# MCU.net
KiCad netlist of a schematic drawn in Altium Designer
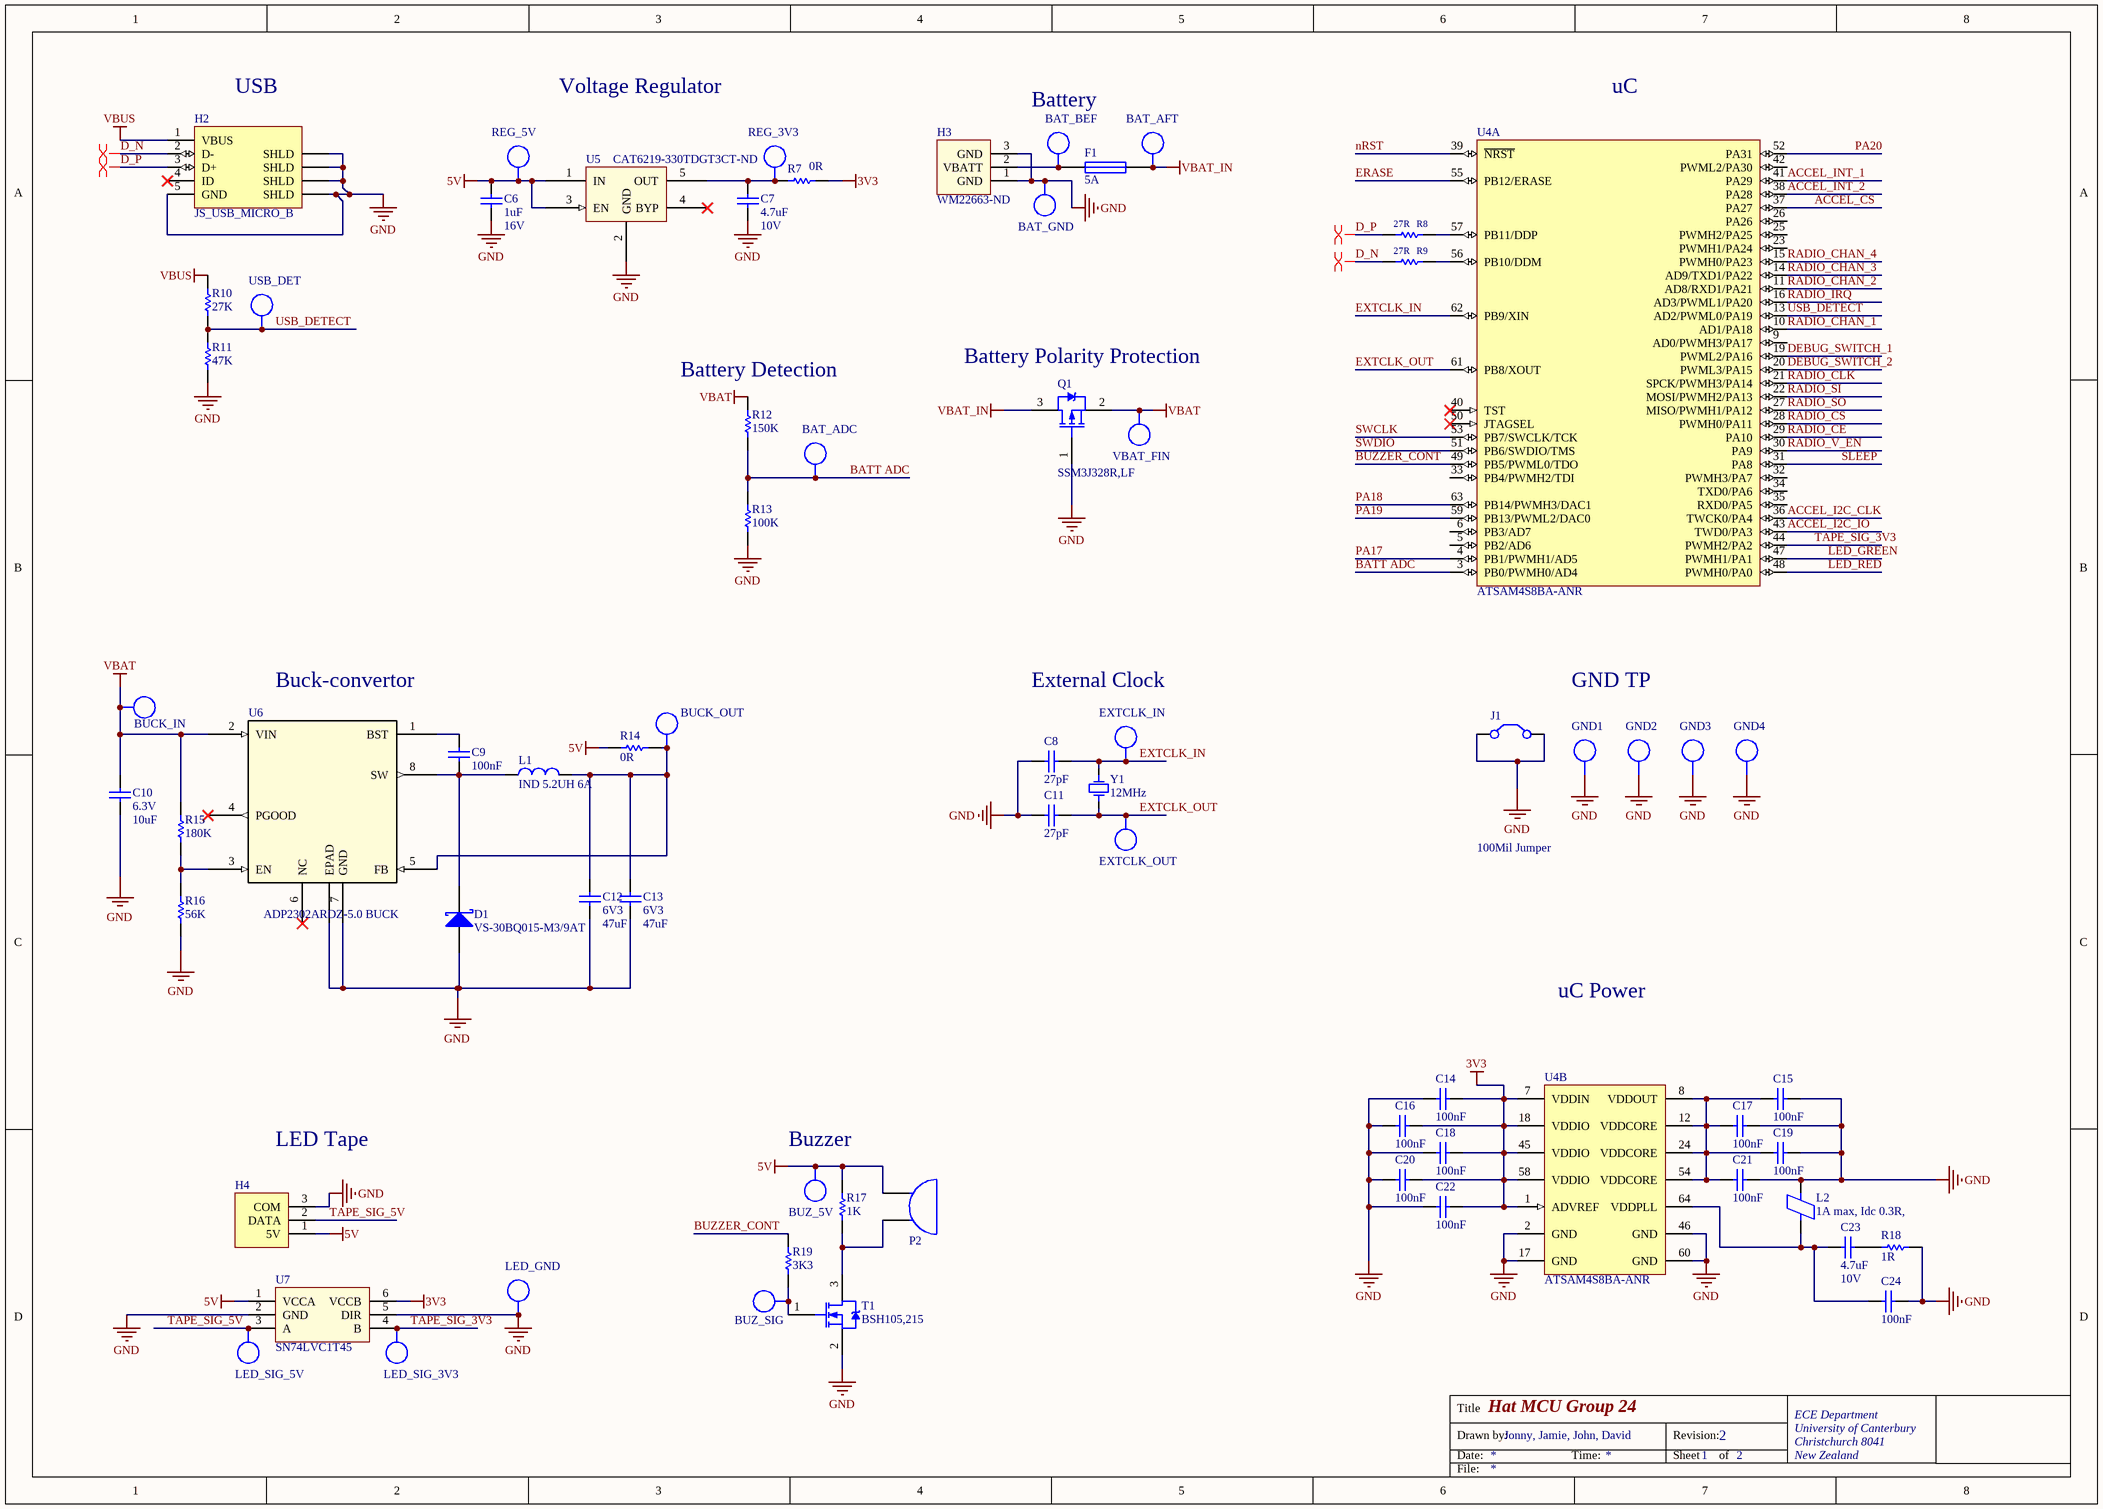
[diagram p0: MCU.SchDoc]

(export (version "E")
  (design (tool "Eeschema 10.0.6"))
  (components
    (comp (ref "BAT_ADC")
      (value "TP")
      (footprint "TP_1206")
      (description "Test-Point 3.3x1.6x2.1mm SMD")
      (fields
        (field (name "MANUFACTURER") "Harwin Inc")
        (field (name "MANUFACTURER PART NUMBER") "S1751-46R")
      )
      (libsource (lib "ECE AD19Components_22V1") (part "TP_1206"))
    )
    (comp (ref "BAT_AFT")
      (value "TP")
      (footprint "TP_1206")
      (description "Test-Point 3.3x1.6x2.1mm SMD")
      (fields
        (field (name "MANUFACTURER") "Harwin Inc")
        (field (name "MANUFACTURER PART NUMBER") "S1751-46R")
      )
      (libsource (lib "ECE AD19Components_22V1") (part "TP_1206"))
    )
    (comp (ref "BAT_BEF")
      (value "TP")
      (footprint "TP_1206")
      (description "Test-Point 3.3x1.6x2.1mm SMD")
      (fields
        (field (name "MANUFACTURER") "Harwin Inc")
        (field (name "MANUFACTURER PART NUMBER") "S1751-46R")
      )
      (libsource (lib "ECE AD19Components_22V1") (part "TP_1206"))
    )
    (comp (ref "BAT_GND")
      (value "TP")
      (footprint "TP_1206")
      (description "Test-Point 3.3x1.6x2.1mm SMD")
      (fields
        (field (name "MANUFACTURER") "Harwin Inc")
        (field (name "MANUFACTURER PART NUMBER") "S1751-46R")
      )
      (libsource (lib "ECE AD19Components_22V1") (part "TP_1206"))
    )
    (comp (ref "BUCK_IN")
      (value "TP")
      (footprint "TP_1206")
      (description "Test-Point 3.3x1.6x2.1mm SMD")
      (fields
        (field (name "MANUFACTURER") "Harwin Inc")
        (field (name "MANUFACTURER PART NUMBER") "S1751-46R")
      )
      (libsource (lib "ECE AD19Components_22V1") (part "TP_1206"))
    )
    (comp (ref "BUCK_OUT")
      (value "TP")
      (footprint "TP_1206")
      (description "Test-Point 3.3x1.6x2.1mm SMD")
      (fields
        (field (name "MANUFACTURER") "Harwin Inc")
        (field (name "MANUFACTURER PART NUMBER") "S1751-46R")
      )
      (libsource (lib "ECE AD19Components_22V1") (part "TP_1206"))
    )
    (comp (ref "BUZ_5V")
      (value "TP")
      (footprint "TP_1206")
      (description "Test-Point 3.3x1.6x2.1mm SMD")
      (fields
        (field (name "MANUFACTURER") "Harwin Inc")
        (field (name "MANUFACTURER PART NUMBER") "S1751-46R")
      )
      (libsource (lib "ECE AD19Components_22V1") (part "TP_1206"))
    )
    (comp (ref "BUZ_SIG")
      (value "TP")
      (footprint "TP_1206")
      (description "Test-Point 3.3x1.6x2.1mm SMD")
      (fields
        (field (name "MANUFACTURER") "Harwin Inc")
        (field (name "MANUFACTURER PART NUMBER") "S1751-46R")
      )
      (libsource (lib "ECE AD19Components_22V1") (part "TP_1206"))
    )
    (comp (ref "C6")
      (value "1uF")
      (footprint "CAPC1608L")
      (description "CAP CER 1uF Y5V -20% +80% 16V 0603")
      (fields (field (name "MAX VOLTAGE") "16V"))
      (libsource (lib "ECE AD19Components_22V1") (part "CC_1uF_0603"))
    )
    (comp (ref "C7")
      (value "4.7uF")
      (footprint "CAPC1608N")
      (description "CAP CER 4.7uF X5R +-20%  10V 0603")
      (fields (field (name "MAX VOLTAGE") "10V"))
      (libsource (lib "ECE AD19Components_22V1") (part "CC_4.7uF_0603"))
    )
    (comp (ref "C8")
      (value "27pF")
      (footprint "CAPC1608L")
      (description "CAP CER 27pF NPO/COG +-5% 50V 0603")
      (libsource (lib "ECE AD19Components_22V1") (part "CC_27pF_0603"))
    )
    (comp (ref "C9")
      (value "100nF")
      (footprint "CAPC1608L")
      (description "CAP CER 100nF X7R +-10% 50V 0603")
      (libsource (lib "ECE AD19Components_22V1") (part "CC_100nF_0603"))
    )
    (comp (ref "C10")
      (value "10uF")
      (footprint "CAPC1608L")
      (description "CAP CER 10UF X5R +-20% 6V3 0603")
      (fields (field (name "VOLTAGE - RATED") "6.3V"))
      (libsource (lib "ECE AD19Components_22V1") (part "CC_10uF_0603"))
    )
    (comp (ref "C11")
      (value "27pF")
      (footprint "CAPC1608L")
      (description "CAP CER 27pF NPO/COG +-5% 50V 0603")
      (libsource (lib "ECE AD19Components_22V1") (part "CC_27pF_0603"))
    )
    (comp (ref "C12")
      (value "CC_47uF_0805_6V3")
      (footprint "CAPC2012N")
      (description "SAMSUNG ELECTRO-MECHANICS - CL21A476MQCLRNC - CAP, 47UF, 6.3V, MLCC, 0805")
      (fields
        (field (name "TOLERANCE") "20%")
        (field (name "VOLTAGE RATING") "6V3")
        (field (name "CAPACITANCE") "47uF")
      )
      (libsource (lib "ECE AD19Components_22V1") (part "CC_47uF_0805_6V3"))
    )
    (comp (ref "C13")
      (value "CC_47uF_0805_6V3")
      (footprint "CAPC2012N")
      (description "SAMSUNG ELECTRO-MECHANICS - CL21A476MQCLRNC - CAP, 47UF, 6.3V, MLCC, 0805")
      (fields
        (field (name "TOLERANCE") "20%")
        (field (name "VOLTAGE RATING") "6V3")
        (field (name "CAPACITANCE") "47uF")
      )
      (libsource (lib "ECE AD19Components_22V1") (part "CC_47uF_0805_6V3"))
    )
    (comp (ref "C14")
      (value "100nF")
      (footprint "CAPC1608L")
      (description "CAP CER 100nF X7R +-10% 50V 0603")
      (libsource (lib "ECE AD19Components_22V1") (part "CC_100nF_0603"))
    )
    (comp (ref "C15")
      (value "100nF")
      (footprint "CAPC1608L")
      (description "CAP CER 100nF X7R +-10% 50V 0603")
      (libsource (lib "ECE AD19Components_22V1") (part "CC_100nF_0603"))
    )
    (comp (ref "C16")
      (value "100nF")
      (footprint "CAPC1608L")
      (description "CAP CER 100nF X7R +-10% 50V 0603")
      (libsource (lib "ECE AD19Components_22V1") (part "CC_100nF_0603"))
    )
    (comp (ref "C17")
      (value "100nF")
      (footprint "CAPC1608L")
      (description "CAP CER 100nF X7R +-10% 50V 0603")
      (libsource (lib "ECE AD19Components_22V1") (part "CC_100nF_0603"))
    )
    (comp (ref "C18")
      (value "100nF")
      (footprint "CAPC1608L")
      (description "CAP CER 100nF X7R +-10% 50V 0603")
      (libsource (lib "ECE AD19Components_22V1") (part "CC_100nF_0603"))
    )
    (comp (ref "C19")
      (value "100nF")
      (footprint "CAPC1608L")
      (description "CAP CER 100nF X7R +-10% 50V 0603")
      (libsource (lib "ECE AD19Components_22V1") (part "CC_100nF_0603"))
    )
    (comp (ref "C20")
      (value "100nF")
      (footprint "CAPC1608L")
      (description "CAP CER 100nF X7R +-10% 50V 0603")
      (libsource (lib "ECE AD19Components_22V1") (part "CC_100nF_0603"))
    )
    (comp (ref "C21")
      (value "100nF")
      (footprint "CAPC1608L")
      (description "CAP CER 100nF X7R +-10% 50V 0603")
      (libsource (lib "ECE AD19Components_22V1") (part "CC_100nF_0603"))
    )
    (comp (ref "C22")
      (value "100nF")
      (footprint "CAPC1608L")
      (description "CAP CER 100nF X7R +-10% 50V 0603")
      (libsource (lib "ECE AD19Components_22V1") (part "CC_100nF_0603"))
    )
    (comp (ref "C23")
      (value "4.7uF")
      (footprint "CAPC1608N")
      (description "CAP CER 4.7uF X5R +-20%  10V 0603")
      (fields (field (name "MAX VOLTAGE") "10V"))
      (libsource (lib "ECE AD19Components_22V1") (part "CC_4.7uF_0603"))
    )
    (comp (ref "C24")
      (value "100nF")
      (footprint "CAPC1608L")
      (description "CAP CER 100nF X7R +-10% 50V 0603")
      (libsource (lib "ECE AD19Components_22V1") (part "CC_100nF_0603"))
    )
    (comp (ref "D1")
      (value "VS-30BQ015-M3/9AT")
      (footprint "SMC")
      (description "DIODE, SCHOTTKY, 3A, 15V, DO-214AB / SMC")
      (fields (field (name "MANUFACTURER") "Vishay Semiconductors"))
      (libsource (lib "ECE AD19Components_22V1") (part "DS_VS-30BQ015-M3"))
    )
    (comp (ref "EXTCLK_IN")
      (value "TP")
      (footprint "TP_1206")
      (description "Test-Point 3.3x1.6x2.1mm SMD")
      (fields
        (field (name "MANUFACTURER") "Harwin Inc")
        (field (name "MANUFACTURER PART NUMBER") "S1751-46R")
      )
      (libsource (lib "ECE AD19Components_22V1") (part "TP_1206"))
    )
    (comp (ref "EXTCLK_OUT")
      (value "TP")
      (footprint "TP_1206")
      (description "Test-Point 3.3x1.6x2.1mm SMD")
      (fields
        (field (name "MANUFACTURER") "Harwin Inc")
        (field (name "MANUFACTURER PART NUMBER") "S1751-46R")
      )
      (libsource (lib "ECE AD19Components_22V1") (part "TP_1206"))
    )
    (comp (ref "F1")
      (value "5A")
      (footprint "RESC3216N")
      (description "Fuse 5.0A Fast Acting 1206 SMD")
      (fields (field (name "MANUFACTURER PART NUMBER") "C1F5") (field (name "MANUFACTURER") "Bel TRP"))
      (libsource (lib "ECE AD19Components_22V1") (part "FS_Fuse_5.0A"))
    )
    (comp (ref "GND1")
      (value "TP")
      (footprint "TP_1206")
      (description "Test-Point 3.3x1.6x2.1mm SMD")
      (fields
        (field (name "MANUFACTURER") "Harwin Inc")
        (field (name "MANUFACTURER PART NUMBER") "S1751-46R")
      )
      (libsource (lib "ECE AD19Components_22V1") (part "TP_1206"))
    )
    (comp (ref "GND2")
      (value "TP")
      (footprint "TP_1206")
      (description "Test-Point 3.3x1.6x2.1mm SMD")
      (fields
        (field (name "MANUFACTURER") "Harwin Inc")
        (field (name "MANUFACTURER PART NUMBER") "S1751-46R")
      )
      (libsource (lib "ECE AD19Components_22V1") (part "TP_1206"))
    )
    (comp (ref "GND3")
      (value "TP")
      (footprint "TP_1206")
      (description "Test-Point 3.3x1.6x2.1mm SMD")
      (fields
        (field (name "MANUFACTURER") "Harwin Inc")
        (field (name "MANUFACTURER PART NUMBER") "S1751-46R")
      )
      (libsource (lib "ECE AD19Components_22V1") (part "TP_1206"))
    )
    (comp (ref "GND4")
      (value "TP")
      (footprint "TP_1206")
      (description "Test-Point 3.3x1.6x2.1mm SMD")
      (fields
        (field (name "MANUFACTURER") "Harwin Inc")
        (field (name "MANUFACTURER PART NUMBER") "S1751-46R")
      )
      (libsource (lib "ECE AD19Components_22V1") (part "TP_1206"))
    )
    (comp (ref "H2")
      (value "JS_USB_MICRO_B")
      (footprint "FCI_USB_10118194-0001LF")
      (description "CONN USB MICRO B RECPT SMT R/A")
      (fields (field (name "MANUFACTURER") "FCI") (field (name "MANUFACTURER PART NUMBER") "10118194-0001LF"))
      (libsource (lib "ECE AD19Components_22V1") (part "JS_USB_MICRO_B_SMT"))
    )
    (comp (ref "H3")
      (value "Battery_HEADER_3pin")
      (footprint "BATT_HEADER_3POS")
      (description "3Pin Header 2.54mm spacing\r\nDigikey #WM22663-ND")
      (fields (field (name "SUPPLIER PART NUMBER 1") "WM22663-ND"))
      (libsource (lib "ENCE461AD19_V23") (part "Battery_HEADER_3pin"))
    )
    (comp (ref "H4")
      (value "3 Pin Molex KK Hdr")
      (footprint "MOLEX_KK_3_HDR")
      (description "CONN HEADER 3POS 2.54mm VERT_Thru Hole")
      (fields (field (name "MANUFACTURER") "Molex"))
      (libsource (lib "ENCE461AD19_V23") (part "LED_Strip_Header"))
    )
    (comp (ref "J1")
      (value "100Mil Jumper")
      (footprint "JMP2.54")
      (description "2.54mm Jumper Thru Hole")
      (libsource (lib "ECE AD19Components_22V1") (part "TP_JUMPER"))
    )
    (comp (ref "L1")
      (value "IND 5.2UH 6A")
      (footprint "INDUCTOR5u2")
      (description "FIXED IND 5.2UH 6A 22 MOHM SMD")
      (fields
        (field (name "MANUFACTURER") "Sumida America Components Inc.")
        (field (name "MANUFACTURER PART NUMBER") "CDRH104RNP-5R2NC")
      )
      (libsource (lib "ENCE461AD19_V23") (part "CDRH104RNP-5R2NC"))
    )
    (comp (ref "L2")
      (value "1A max, Idc 0.3R,")
      (footprint "INDC3216L")
      (description "Ferrite Bead, Rdc 0.3R, Z100MHZ 600R, Imax 1A, SMD 1206")
      (fields
        (field (name "MANUFACTURER") "FAIR-RITE")
        (field (name "MANUFACTURER PART NUMBER") "2512066017Y1")
      )
      (libsource (lib "ECE AD19Components_22V1") (part "IN_Ferrite-Bead"))
    )
    (comp (ref "LED_GND")
      (value "TP")
      (footprint "TP_1206")
      (description "Test-Point 3.3x1.6x2.1mm SMD")
      (fields
        (field (name "MANUFACTURER") "Harwin Inc")
        (field (name "MANUFACTURER PART NUMBER") "S1751-46R")
      )
      (libsource (lib "ECE AD19Components_22V1") (part "TP_1206"))
    )
    (comp (ref "LED_SIG_3V3")
      (value "TP")
      (footprint "TP_1206")
      (description "Test-Point 3.3x1.6x2.1mm SMD")
      (fields
        (field (name "MANUFACTURER") "Harwin Inc")
        (field (name "MANUFACTURER PART NUMBER") "S1751-46R")
      )
      (libsource (lib "ECE AD19Components_22V1") (part "TP_1206"))
    )
    (comp (ref "LED_SIG_5V")
      (value "TP")
      (footprint "TP_1206")
      (description "Test-Point 3.3x1.6x2.1mm SMD")
      (fields
        (field (name "MANUFACTURER") "Harwin Inc")
        (field (name "MANUFACTURER PART NUMBER") "S1751-46R")
      )
      (libsource (lib "ECE AD19Components_22V1") (part "TP_1206"))
    )
    (comp (ref "P2")
      (value "Piezo Buzzer")
      (footprint "BUZZER")
      (description "TDK - PS1240P02BT - BUZZER, PIEZO, 70DB, 12.2MM")
      (libsource (lib "ENCE461AD19_V23") (part "Piezo Buzzer"))
    )
    (comp (ref "Q1")
      (value "SSM3J328R,LF")
      (footprint "SOT23_L")
      (description "MOSFET P-CH 20V 6A SOT23-3")
      (fields
        (field (name "MANUFACTURER") "Toshiba")
        (field (name "MANUFACTURER PART NUMBER") "SSM3J328R,LF")
      )
      (libsource (lib "ECE AD19Components_22V1") (part "TM_SSM3J328R"))
    )
    (comp (ref "R7")
      (value "0R")
      (footprint "RESC1608L")
      (description "RES 0.0 OHM 1/10W 5% 0603 SMD")
      (libsource (lib "ECE AD19Components_22V1") (part "RS_0R0"))
    )
    (comp (ref "R8")
      (value "27R")
      (footprint "RESC1608L")
      (description "RES 27 OHM 1/10W 5% 0603 SMD")
      (libsource (lib "ECE AD19Components_22V1") (part "RS_27R"))
    )
    (comp (ref "R9")
      (value "27R")
      (footprint "RESC1608L")
      (description "RES 27 OHM 1/10W 5% 0603 SMD")
      (libsource (lib "ECE AD19Components_22V1") (part "RS_27R"))
    )
    (comp (ref "R10")
      (value "27K")
      (footprint "RESC1608L")
      (description "RES 27K OHM 1/10W 5% 0603 SMD")
      (libsource (lib "ECE AD19Components_22V1") (part "RS_27K"))
    )
    (comp (ref "R11")
      (value "47K")
      (footprint "RESC1608N")
      (description "RES 47.0K OHM 1/10W 5% 0603 SMD")
      (libsource (lib "ECE AD19Components_22V1") (part "RS_47K"))
    )
    (comp (ref "R12")
      (value "150K")
      (footprint "RESC1608L")
      (description "RES 150K OHM 1/10W 5% 0603 SMD")
      (libsource (lib "ECE AD19Components_22V1") (part "RS_150K"))
    )
    (comp (ref "R13")
      (value "100K")
      (footprint "RESC1608L")
      (description "RES 100K OHM 1/10W 5% 0603 SMD")
      (libsource (lib "ECE AD19Components_22V1") (part "RS_100K"))
    )
    (comp (ref "R14")
      (value "0R")
      (footprint "RESC1608L")
      (description "RES 0.0 OHM 1/10W 5% 0603 SMD")
      (libsource (lib "ECE AD19Components_22V1") (part "RS_0R0"))
    )
    (comp (ref "R15")
      (value "180K")
      (footprint "RESC1608L")
      (description "RES 180K OHM 1/10W 5% 0603 SMD")
      (libsource (lib "ECE AD19Components_22V1") (part "RS_180K"))
    )
    (comp (ref "R16")
      (value "56K")
      (footprint "RESC1608L")
      (description "RES 56.0K OHM 1/10W 5% 0603 SMD")
      (libsource (lib "ECE AD19Components_22V1") (part "RS_56K"))
    )
    (comp (ref "R17")
      (value "1K")
      (footprint "RESC1608L")
      (description "RES 1.0K OHM 1/10W 5% 0603 SMD")
      (libsource (lib "ECE AD19Components_22V1") (part "RS_1K"))
    )
    (comp (ref "R18")
      (value "1R")
      (footprint "RESC3216L")
      (description "RES 1R OHM 1/4W 5% 1206 SMD")
      (libsource (lib "ECE AD19Components_22V1") (part "RT_1R"))
    )
    (comp (ref "R19")
      (value "3K3")
      (footprint "RESC1608L")
      (description "RES 3.3K OHM 1/10W 5% 0603 SMD")
      (libsource (lib "ECE AD19Components_22V1") (part "RS_3K3"))
    )
    (comp (ref "REG_3V3")
      (value "TP")
      (footprint "TP_1206")
      (description "Test-Point 3.3x1.6x2.1mm SMD")
      (fields
        (field (name "MANUFACTURER") "Harwin Inc")
        (field (name "MANUFACTURER PART NUMBER") "S1751-46R")
      )
      (libsource (lib "ECE AD19Components_22V1") (part "TP_1206"))
    )
    (comp (ref "REG_5V")
      (value "TP")
      (footprint "TP_1206")
      (description "Test-Point 3.3x1.6x2.1mm SMD")
      (fields
        (field (name "MANUFACTURER") "Harwin Inc")
        (field (name "MANUFACTURER PART NUMBER") "S1751-46R")
      )
      (libsource (lib "ECE AD19Components_22V1") (part "TP_1206"))
    )
    (comp (ref "T1")
      (value "BSH105,215")
      (footprint "SOT23_L")
      (description "MOSFET N-CH 20V 1.05A SOT-23")
      (fields
        (field (name "MANUFACTURER") "NXP Semiconductors")
        (field (name "MANUFACTURER PART NUMBER") "BSH105,215")
      )
      (libsource (lib "ECE AD19Components_22V1") (part "TM_BSH105"))
    )
    (comp (ref "U4")
      (value "ATSAM4S8BA-ANR")
      (footprint "LQFP64_L")
      (description "IC MCU 32BIT 512KB FLASH 64LQFP")
      (fields (field (name "MANUFACTURER") "Atmel"))
      (libsource (lib "ECE AD19Components_22V1") (part "SE_ATSAM4S16BA-MU"))
    )
    (comp (ref "U5")
      (value "CAT6219-330TDGT3")
      (footprint "SOT95P280X145-5N")
      (description "IC REG LIN 3.3V 500MA TSOT23-5")
      (fields
        (field (name "BASE PART NUMBER") "CAT6219")
        (field (name "SUPPLIER PART NUMBER") "CAT6219-330TDGT3CT-ND")
      )
      (libsource (lib "ENCE461AD19_V23") (part "SV_CAT6219-330TDGT3"))
    )
    (comp (ref "U6")
      (value "ADP2302ARDZ-5.0 BUCK")
      (footprint "RD_8_1")
      (description "IC REG BUCK 5V 2A 8SOIC")
      (fields (field (name "MANUFACTURER_PART_NUMBER") "ADP2302ARDZ-5.0-R7"))
      (libsource (lib "ENCE461AD19_V23") (part "ADP2302ARDZ-5.0-R7"))
    )
    (comp (ref "U7")
      (value "SN74LVC1T45")
      (footprint "SOT23-6_N")
      (description "1.8V - 5V level converter")
      (libsource (lib "ENCE461AD19_V23") (part "SN74LVC1T45"))
    )
    (comp (ref "USB_DET")
      (value "TP")
      (footprint "TP_1206")
      (description "Test-Point 3.3x1.6x2.1mm SMD")
      (fields
        (field (name "MANUFACTURER") "Harwin Inc")
        (field (name "MANUFACTURER PART NUMBER") "S1751-46R")
      )
      (libsource (lib "ECE AD19Components_22V1") (part "TP_1206"))
    )
    (comp (ref "VBAT_FIN")
      (value "TP")
      (footprint "TP_1206")
      (description "Test-Point 3.3x1.6x2.1mm SMD")
      (fields
        (field (name "MANUFACTURER") "Harwin Inc")
        (field (name "MANUFACTURER PART NUMBER") "S1751-46R")
      )
      (libsource (lib "ECE AD19Components_22V1") (part "TP_1206"))
    )
    (comp (ref "Y1")
      (value "12MHz")
      (footprint "6.0X3.5-4")
      (description "CRYSTAL 12MHZ 18PF 6X3.5mm SMD")
      (fields
        (field (name "MANUFACTURER") "CTS-Frequency Controls")
        (field (name "MANUFACTURER PART NUMBER") "406C35D12M00000")
        (field (name "FREQUENCY") "12MHz")
      )
      (libsource (lib "ECE AD19Components_22V1") (part "XT_CRYSTAL_12MHz_18pF"))
    )
  )
  (nets
    (net (code "1") (name "/ACCEL_CS") (class "Default")
      (node (ref "U4") (pin "37") (pinfunction "PA27_37") (pintype "bidirectional"))
    )
    (net (code "2") (name "/ACCEL_I2C_CLK") (class "Default")
      (node (ref "U4") (pin "36") (pinfunction "TWCK0/PA4_36") (pintype "bidirectional"))
    )
    (net (code "3") (name "/ACCEL_I2C_IO") (class "Default")
      (node (ref "U4") (pin "43") (pinfunction "TWD0/PA3_43") (pintype "bidirectional"))
    )
    (net (code "4") (name "/ACCEL_INT_1") (class "Default")
      (node (ref "U4") (pin "41") (pinfunction "PA29_41") (pintype "bidirectional"))
    )
    (net (code "5") (name "/ACCEL_INT_2") (class "Default")
      (node (ref "U4") (pin "38") (pinfunction "PA28_38") (pintype "bidirectional"))
    )
    (net (code "6") (name "/BATT ADC") (class "Default")
      (node (ref "BAT_ADC") (pin "1") (pinfunction "1_1") (pintype "passive"))
      (node (ref "R12") (pin "1") (pinfunction "1_1") (pintype "passive"))
      (node (ref "R13") (pin "2") (pinfunction "2_2") (pintype "passive"))
      (node (ref "U4") (pin "3") (pinfunction "PB0/PWMH0/AD4_3") (pintype "bidirectional"))
    )
    (net (code "7") (name "/BUZZER_CONT") (class "Default")
      (node (ref "R19") (pin "1") (pinfunction "1_1") (pintype "passive"))
      (node (ref "U4") (pin "49") (pinfunction "PB5/PWML0/TDO_49") (pintype "bidirectional"))
    )
    (net (code "8") (name "/DEBUG_SWITCH_1") (class "Default")
      (node (ref "U4") (pin "19") (pinfunction "PWML2/PA16_19") (pintype "bidirectional"))
    )
    (net (code "9") (name "/DEBUG_SWITCH_2") (class "Default")
      (node (ref "U4") (pin "20") (pinfunction "PWML3/PA15_20") (pintype "bidirectional"))
    )
    (net (code "10") (name "/D_N") (class "Default")
      (node (ref "H2") (pin "2") (pinfunction "D-_2") (pintype "bidirectional"))
      (node (ref "R9") (pin "1") (pinfunction "1_1") (pintype "passive"))
    )
    (net (code "11") (name "/D_P") (class "Default")
      (node (ref "H2") (pin "3") (pinfunction "D+_3") (pintype "bidirectional"))
      (node (ref "R8") (pin "1") (pinfunction "1_1") (pintype "passive"))
    )
    (net (code "12") (name "/ERASE") (class "Default")
      (node (ref "U4") (pin "55") (pinfunction "PB12/ERASE_55") (pintype "bidirectional"))
    )
    (net (code "13") (name "/EXTCLK_IN") (class "Default")
      (node (ref "C8") (pin "2") (pinfunction "2_2") (pintype "passive"))
      (node (ref "EXTCLK_IN") (pin "1") (pinfunction "1_1") (pintype "passive"))
      (node (ref "U4") (pin "62") (pinfunction "PB9/XIN_62") (pintype "bidirectional"))
      (node (ref "Y1") (pin "3") (pinfunction "OSC2_3") (pintype "passive"))
    )
    (net (code "14") (name "/EXTCLK_OUT") (class "Default")
      (node (ref "C11") (pin "2") (pinfunction "2_2") (pintype "passive"))
      (node (ref "EXTCLK_OUT") (pin "1") (pinfunction "1_1") (pintype "passive"))
      (node (ref "U4") (pin "61") (pinfunction "PB8/XOUT_61") (pintype "bidirectional"))
      (node (ref "Y1") (pin "1") (pinfunction "OSC1_1") (pintype "passive"))
    )
    (net (code "15") (name "/LED_GREEN") (class "Default")
      (node (ref "U4") (pin "47") (pinfunction "PWMH1/PA1_47") (pintype "bidirectional"))
    )
    (net (code "16") (name "/LED_RED") (class "Default")
      (node (ref "U4") (pin "48") (pinfunction "PWMH0/PA0_48") (pintype "bidirectional"))
    )
    (net (code "17") (name "/PA17") (class "Default")
      (node (ref "U4") (pin "4") (pinfunction "PB1/PWMH1/AD5_4") (pintype "bidirectional"))
    )
    (net (code "18") (name "/PA18") (class "Default")
      (node (ref "U4") (pin "63") (pinfunction "PB14/PWMH3/DAC1_63") (pintype "bidirectional"))
    )
    (net (code "19") (name "/PA19") (class "Default")
      (node (ref "U4") (pin "59") (pinfunction "PB13/PWML2/DAC0_59") (pintype "bidirectional"))
    )
    (net (code "20") (name "/PA20") (class "Default")
      (node (ref "U4") (pin "52") (pinfunction "PA31_52") (pintype "bidirectional"))
    )
    (net (code "21") (name "/RADIO_CE") (class "Default")
      (node (ref "U4") (pin "29") (pinfunction "PA10_29") (pintype "bidirectional"))
    )
    (net (code "22") (name "/RADIO_CHAN_1") (class "Default")
      (node (ref "U4") (pin "10") (pinfunction "AD1/PA18_10") (pintype "bidirectional"))
    )
    (net (code "23") (name "/RADIO_CHAN_2") (class "Default")
      (node (ref "U4") (pin "11") (pinfunction "AD8/RXD1/PA21_11") (pintype "bidirectional"))
    )
    (net (code "24") (name "/RADIO_CHAN_3") (class "Default")
      (node (ref "U4") (pin "14") (pinfunction "AD9/TXD1/PA22_14") (pintype "bidirectional"))
    )
    (net (code "25") (name "/RADIO_CHAN_4") (class "Default")
      (node (ref "U4") (pin "15") (pinfunction "PWMH0/PA23_15") (pintype "bidirectional"))
    )
    (net (code "26") (name "/RADIO_CLK") (class "Default")
      (node (ref "U4") (pin "21") (pinfunction "SPCK/PWMH3/PA14_21") (pintype "bidirectional"))
    )
    (net (code "27") (name "/RADIO_CS") (class "Default")
      (node (ref "U4") (pin "28") (pinfunction "PWMH0/PA11_28") (pintype "bidirectional"))
    )
    (net (code "28") (name "/RADIO_IRQ") (class "Default")
      (node (ref "U4") (pin "16") (pinfunction "AD3/PWML1/PA20_16") (pintype "bidirectional"))
    )
    (net (code "29") (name "/RADIO_SI") (class "Default")
      (node (ref "U4") (pin "22") (pinfunction "MOSI/PWMH2/PA13_22") (pintype "bidirectional"))
    )
    (net (code "30") (name "/RADIO_SO") (class "Default")
      (node (ref "U4") (pin "27") (pinfunction "MISO/PWMH1/PA12_27") (pintype "bidirectional"))
    )
    (net (code "31") (name "/RADIO_V_EN") (class "Default")
      (node (ref "U4") (pin "30") (pinfunction "PA9_30") (pintype "bidirectional"))
    )
    (net (code "32") (name "/SLEEP") (class "Default")
      (node (ref "U4") (pin "31") (pinfunction "PA8_31") (pintype "bidirectional"))
    )
    (net (code "33") (name "/SWCLK") (class "Default")
      (node (ref "U4") (pin "53") (pinfunction "PB7/SWCLK/TCK_53") (pintype "bidirectional"))
    )
    (net (code "34") (name "/SWDIO") (class "Default")
      (node (ref "U4") (pin "51") (pinfunction "PB6/SWDIO/TMS_51") (pintype "bidirectional"))
    )
    (net (code "35") (name "/TAPE_SIG_3V3") (class "Default")
      (node (ref "LED_SIG_3V3") (pin "1") (pinfunction "1_1") (pintype "passive"))
      (node (ref "U4") (pin "44") (pinfunction "PWMH2/PA2_44") (pintype "bidirectional"))
      (node (ref "U7") (pin "4") (pinfunction "B_4") (pintype "passive"))
    )
    (net (code "36") (name "/TAPE_SIG_5V") (class "Default")
      (node (ref "H4") (pin "2") (pinfunction "DATA_2") (pintype "passive"))
      (node (ref "LED_SIG_5V") (pin "1") (pinfunction "1_1") (pintype "passive"))
      (node (ref "U7") (pin "3") (pinfunction "A_3") (pintype "passive"))
    )
    (net (code "37") (name "/USB_DETECT") (class "Default")
      (node (ref "R10") (pin "2") (pinfunction "2_2") (pintype "passive"))
      (node (ref "R11") (pin "2") (pinfunction "2_2") (pintype "passive"))
      (node (ref "U4") (pin "13") (pinfunction "AD2/PWML0/PA19_13") (pintype "bidirectional"))
      (node (ref "USB_DET") (pin "1") (pinfunction "1_1") (pintype "passive"))
    )
    (net (code "38") (name "/nRST") (class "Default")
      (node (ref "U4") (pin "39") (pinfunction "~{NRST}_39") (pintype "bidirectional"))
    )
    (net (code "39") (name "3V3") (class "Default")
      (node (ref "C14") (pin "2") (pinfunction "2_2") (pintype "passive"))
      (node (ref "C16") (pin "2") (pinfunction "2_2") (pintype "passive"))
      (node (ref "C18") (pin "2") (pinfunction "2_2") (pintype "passive"))
      (node (ref "C20") (pin "2") (pinfunction "2_2") (pintype "passive"))
      (node (ref "C22") (pin "2") (pinfunction "2_2") (pintype "passive"))
      (node (ref "R7") (pin "2") (pinfunction "2_2") (pintype "passive"))
      (node (ref "U4") (pin "1") (pinfunction "ADVREF_1") (pintype "input"))
      (node (ref "U4") (pin "18") (pinfunction "VDDIO_18") (pintype "power_in"))
      (node (ref "U4") (pin "45") (pinfunction "VDDIO_45") (pintype "power_in"))
      (node (ref "U4") (pin "58") (pinfunction "VDDIO_58") (pintype "power_in"))
      (node (ref "U4") (pin "7") (pinfunction "VDDIN_7") (pintype "power_in"))
      (node (ref "U7") (pin "6") (pinfunction "VCCB_6") (pintype "passive"))
    )
    (net (code "40") (name "5V") (class "Default")
      (node (ref "BUZ_5V") (pin "1") (pinfunction "1_1") (pintype "passive"))
      (node (ref "C6") (pin "1") (pinfunction "1_1") (pintype "passive"))
      (node (ref "H4") (pin "1") (pinfunction "5V_1") (pintype "passive"))
      (node (ref "P2") (pin "1") (pinfunction "1_1") (pintype "passive"))
      (node (ref "R14") (pin "2") (pinfunction "2_2") (pintype "passive"))
      (node (ref "R17") (pin "2") (pinfunction "2_2") (pintype "passive"))
      (node (ref "REG_5V") (pin "1") (pinfunction "1_1") (pintype "passive"))
      (node (ref "U5") (pin "1") (pinfunction "IN_1") (pintype "power_in"))
      (node (ref "U5") (pin "3") (pinfunction "EN_3") (pintype "input"))
      (node (ref "U7") (pin "1") (pinfunction "VCCA_1") (pintype "passive"))
    )
    (net (code "41") (name "GND") (class "Default")
      (node (ref "BAT_GND") (pin "1") (pinfunction "1_1") (pintype "passive"))
      (node (ref "C10") (pin "1") (pinfunction "1_1") (pintype "passive"))
      (node (ref "C11") (pin "1") (pinfunction "1_1") (pintype "passive"))
      (node (ref "C12") (pin "1") (pinfunction "1_1") (pintype "passive"))
      (node (ref "C13") (pin "1") (pinfunction "1_1") (pintype "passive"))
      (node (ref "C14") (pin "1") (pinfunction "1_1") (pintype "passive"))
      (node (ref "C15") (pin "2") (pinfunction "2_2") (pintype "passive"))
      (node (ref "C16") (pin "1") (pinfunction "1_1") (pintype "passive"))
      (node (ref "C17") (pin "2") (pinfunction "2_2") (pintype "passive"))
      (node (ref "C18") (pin "1") (pinfunction "1_1") (pintype "passive"))
      (node (ref "C19") (pin "2") (pinfunction "2_2") (pintype "passive"))
      (node (ref "C20") (pin "1") (pinfunction "1_1") (pintype "passive"))
      (node (ref "C21") (pin "2") (pinfunction "2_2") (pintype "passive"))
      (node (ref "C22") (pin "1") (pinfunction "1_1") (pintype "passive"))
      (node (ref "C24") (pin "1") (pinfunction "1_1") (pintype "passive"))
      (node (ref "C6") (pin "2") (pinfunction "2_2") (pintype "passive"))
      (node (ref "C7") (pin "1") (pinfunction "1_1") (pintype "passive"))
      (node (ref "C8") (pin "1") (pinfunction "1_1") (pintype "passive"))
      (node (ref "D1") (pin "1") (pinfunction "A_1") (pintype "passive"))
      (node (ref "GND1") (pin "1") (pinfunction "1_1") (pintype "passive"))
      (node (ref "GND2") (pin "1") (pinfunction "1_1") (pintype "passive"))
      (node (ref "GND3") (pin "1") (pinfunction "1_1") (pintype "passive"))
      (node (ref "GND4") (pin "1") (pinfunction "1_1") (pintype "passive"))
      (node (ref "H2") (pin "5") (pinfunction "GND_5") (pintype "passive"))
      (node (ref "H2") (pin "6") (pinfunction "SHLD_6") (pintype "passive"))
      (node (ref "H3") (pin "1") (pinfunction "GND_1") (pintype "passive"))
      (node (ref "H3") (pin "3") (pinfunction "GND_3") (pintype "passive"))
      (node (ref "H4") (pin "3") (pinfunction "COM_3") (pintype "passive"))
      (node (ref "J1") (pin "1") (pinfunction "C1_1") (pintype "passive"))
      (node (ref "J1") (pin "2") (pinfunction "C2_2") (pintype "passive"))
      (node (ref "L2") (pin "2") (pinfunction "2_2") (pintype "passive"))
      (node (ref "LED_GND") (pin "1") (pinfunction "1_1") (pintype "passive"))
      (node (ref "Q1") (pin "1") (pinfunction "1_1") (pintype "passive"))
      (node (ref "R11") (pin "1") (pinfunction "1_1") (pintype "passive"))
      (node (ref "R13") (pin "1") (pinfunction "1_1") (pintype "passive"))
      (node (ref "R16") (pin "1") (pinfunction "1_1") (pintype "passive"))
      (node (ref "R18") (pin "1") (pinfunction "1_1") (pintype "passive"))
      (node (ref "T1") (pin "2") (pinfunction "2_2") (pintype "passive"))
      (node (ref "U4") (pin "17") (pinfunction "GND_17") (pintype "power_in"))
      (node (ref "U4") (pin "2") (pinfunction "GND_2") (pintype "power_in"))
      (node (ref "U4") (pin "46") (pinfunction "GND_46") (pintype "power_in"))
      (node (ref "U4") (pin "60") (pinfunction "GND_60") (pintype "power_in"))
      (node (ref "U5") (pin "2") (pinfunction "GND_2") (pintype "power_in"))
      (node (ref "U6") (pin "7") (pinfunction "GND_7") (pintype "power_in"))
      (node (ref "U6") (pin "EPAD") (pinfunction "EPAD_EPAD") (pintype "passive"))
      (node (ref "U7") (pin "2") (pinfunction "GND_2") (pintype "passive"))
      (node (ref "U7") (pin "5") (pinfunction "DIR_5") (pintype "passive"))
    )
    (net (code "42") (name "Net-(BUZ_SIG-Pad1)") (class "Default")
      (node (ref "BUZ_SIG") (pin "1") (pinfunction "1_1") (pintype "passive"))
      (node (ref "R19") (pin "2") (pinfunction "2_2") (pintype "passive"))
      (node (ref "T1") (pin "1") (pinfunction "1_1") (pintype "passive"))
    )
    (net (code "43") (name "Net-(C23-Pad1)") (class "Default")
      (node (ref "C23") (pin "1") (pinfunction "1_1") (pintype "passive"))
      (node (ref "R18") (pin "2") (pinfunction "2_2") (pintype "passive"))
    )
    (net (code "44") (name "Net-(D1-K)") (class "Default")
      (node (ref "C9") (pin "1") (pinfunction "1_1") (pintype "passive"))
      (node (ref "D1") (pin "2") (pinfunction "K_2") (pintype "passive"))
      (node (ref "L1") (pin "1") (pintype "passive"))
      (node (ref "U6") (pin "8") (pinfunction "SW_8") (pintype "output"))
    )
    (net (code "45") (name "Net-(H3-VBATT)") (class "Default")
      (node (ref "BAT_BEF") (pin "1") (pinfunction "1_1") (pintype "passive"))
      (node (ref "F1") (pin "1") (pinfunction "1_1") (pintype "passive"))
      (node (ref "H3") (pin "2") (pinfunction "VBATT_2") (pintype "passive"))
    )
    (net (code "46") (name "Net-(P2-Pad2)") (class "Default")
      (node (ref "P2") (pin "2") (pinfunction "2_2") (pintype "passive"))
      (node (ref "R17") (pin "1") (pinfunction "1_1") (pintype "passive"))
      (node (ref "T1") (pin "3") (pinfunction "3_3") (pintype "passive"))
    )
    (net (code "47") (name "Net-(U4A-PB10{slash}DDM)") (class "Default")
      (node (ref "R9") (pin "2") (pinfunction "2_2") (pintype "passive"))
      (node (ref "U4") (pin "56") (pinfunction "PB10/DDM_56") (pintype "bidirectional"))
    )
    (net (code "48") (name "Net-(U4A-PB11{slash}DDP)") (class "Default")
      (node (ref "R8") (pin "2") (pinfunction "2_2") (pintype "passive"))
      (node (ref "U4") (pin "57") (pinfunction "PB11/DDP_57") (pintype "bidirectional"))
    )
    (net (code "49") (name "Net-(U4B-VDDOUT)") (class "Default")
      (node (ref "C15") (pin "1") (pinfunction "1_1") (pintype "passive"))
      (node (ref "C17") (pin "1") (pinfunction "1_1") (pintype "passive"))
      (node (ref "C19") (pin "1") (pinfunction "1_1") (pintype "passive"))
      (node (ref "C21") (pin "1") (pinfunction "1_1") (pintype "passive"))
      (node (ref "U4") (pin "12") (pinfunction "VDDCORE_12") (pintype "power_in"))
      (node (ref "U4") (pin "24") (pinfunction "VDDCORE_24") (pintype "power_in"))
      (node (ref "U4") (pin "54") (pinfunction "VDDCORE_54") (pintype "power_in"))
      (node (ref "U4") (pin "8") (pinfunction "VDDOUT_8") (pintype "power_in"))
    )
    (net (code "50") (name "Net-(U4B-VDDPLL)") (class "Default")
      (node (ref "C23") (pin "2") (pinfunction "2_2") (pintype "passive"))
      (node (ref "C24") (pin "2") (pinfunction "2_2") (pintype "passive"))
      (node (ref "L2") (pin "1") (pinfunction "1_1") (pintype "passive"))
      (node (ref "U4") (pin "64") (pinfunction "VDDPLL_64") (pintype "power_in"))
    )
    (net (code "51") (name "Net-(U5-OUT)") (class "Default")
      (node (ref "C7") (pin "2") (pinfunction "2_2") (pintype "passive"))
      (node (ref "R7") (pin "1") (pinfunction "1_1") (pintype "passive"))
      (node (ref "REG_3V3") (pin "1") (pinfunction "1_1") (pintype "passive"))
      (node (ref "U5") (pin "5") (pinfunction "OUT_5") (pintype "power_in"))
    )
    (net (code "52") (name "Net-(U6-BST)") (class "Default")
      (node (ref "C9") (pin "2") (pinfunction "2_2") (pintype "passive"))
      (node (ref "U6") (pin "1") (pinfunction "BST_1") (pintype "passive"))
    )
    (net (code "53") (name "Net-(U6-EN)") (class "Default")
      (node (ref "R15") (pin "1") (pinfunction "1_1") (pintype "passive"))
      (node (ref "R16") (pin "2") (pinfunction "2_2") (pintype "passive"))
      (node (ref "U6") (pin "3") (pinfunction "EN_3") (pintype "input"))
    )
    (net (code "54") (name "Net-(U6-FB)") (class "Default")
      (node (ref "BUCK_OUT") (pin "1") (pinfunction "1_1") (pintype "passive"))
      (node (ref "C12") (pin "2") (pinfunction "2_2") (pintype "passive"))
      (node (ref "C13") (pin "2") (pinfunction "2_2") (pintype "passive"))
      (node (ref "L1") (pin "2") (pintype "passive"))
      (node (ref "R14") (pin "1") (pinfunction "1_1") (pintype "passive"))
      (node (ref "U6") (pin "5") (pinfunction "FB_5") (pintype "input"))
    )
    (net (code "55") (name "VBAT") (class "Default")
      (node (ref "BUCK_IN") (pin "1") (pinfunction "1_1") (pintype "passive"))
      (node (ref "C10") (pin "2") (pinfunction "2_2") (pintype "passive"))
      (node (ref "Q1") (pin "2") (pinfunction "2_2") (pintype "passive"))
      (node (ref "R12") (pin "2") (pinfunction "2_2") (pintype "passive"))
      (node (ref "R15") (pin "2") (pinfunction "2_2") (pintype "passive"))
      (node (ref "U6") (pin "2") (pinfunction "VIN_2") (pintype "input"))
      (node (ref "VBAT_FIN") (pin "1") (pinfunction "1_1") (pintype "passive"))
    )
    (net (code "56") (name "VBAT_IN") (class "Default")
      (node (ref "BAT_AFT") (pin "1") (pinfunction "1_1") (pintype "passive"))
      (node (ref "F1") (pin "2") (pinfunction "2_2") (pintype "passive"))
      (node (ref "Q1") (pin "3") (pinfunction "3_3") (pintype "passive"))
    )
    (net (code "57") (name "VBUS") (class "Default")
      (node (ref "H2") (pin "1") (pinfunction "VBUS_1") (pintype "power_in"))
      (node (ref "R10") (pin "1") (pinfunction "1_1") (pintype "passive"))
    )
    (net (code "58") (name "unconnected-(H2-ID-Pad4)") (class "Default")
      (node (ref "H2") (pin "4") (pinfunction "ID_4") (pintype "power_in+no_connect"))
    )
    (net (code "59") (name "unconnected-(U4A-AD0{slash}PWMH3{slash}PA17-Pad9)") (class "Default")
      (node (ref "U4") (pin "9") (pinfunction "AD0/PWMH3/PA17_9") (pintype "bidirectional"))
    )
    (net (code "60") (name "unconnected-(U4A-JTAGSEL-Pad50)") (class "Default")
      (node (ref "U4") (pin "50") (pinfunction "JTAGSEL_50") (pintype "input+no_connect"))
    )
    (net (code "61") (name "unconnected-(U4A-PA26-Pad26)") (class "Default")
      (node (ref "U4") (pin "26") (pinfunction "PA26_26") (pintype "bidirectional"))
    )
    (net (code "62") (name "unconnected-(U4A-PB2{slash}AD6-Pad5)") (class "Default")
      (node (ref "U4") (pin "5") (pinfunction "PB2/AD6_5") (pintype "bidirectional"))
    )
    (net (code "63") (name "unconnected-(U4A-PB3{slash}AD7-Pad6)") (class "Default")
      (node (ref "U4") (pin "6") (pinfunction "PB3/AD7_6") (pintype "bidirectional"))
    )
    (net (code "64") (name "unconnected-(U4A-PB4{slash}PWMH2{slash}TDI-Pad33)") (class "Default")
      (node (ref "U4") (pin "33") (pinfunction "PB4/PWMH2/TDI_33") (pintype "bidirectional"))
    )
    (net (code "65") (name "unconnected-(U4A-PWMH1{slash}PA24-Pad23)") (class "Default")
      (node (ref "U4") (pin "23") (pinfunction "PWMH1/PA24_23") (pintype "bidirectional"))
    )
    (net (code "66") (name "unconnected-(U4A-PWMH2{slash}PA25-Pad25)") (class "Default")
      (node (ref "U4") (pin "25") (pinfunction "PWMH2/PA25_25") (pintype "bidirectional"))
    )
    (net (code "67") (name "unconnected-(U4A-PWMH3{slash}PA7-Pad32)") (class "Default")
      (node (ref "U4") (pin "32") (pinfunction "PWMH3/PA7_32") (pintype "bidirectional"))
    )
    (net (code "68") (name "unconnected-(U4A-PWML2{slash}PA30-Pad42)") (class "Default")
      (node (ref "U4") (pin "42") (pinfunction "PWML2/PA30_42") (pintype "bidirectional"))
    )
    (net (code "69") (name "unconnected-(U4A-RXD0{slash}PA5-Pad35)") (class "Default")
      (node (ref "U4") (pin "35") (pinfunction "RXD0/PA5_35") (pintype "bidirectional"))
    )
    (net (code "70") (name "unconnected-(U4A-TST-Pad40)") (class "Default")
      (node (ref "U4") (pin "40") (pinfunction "TST_40") (pintype "input+no_connect"))
    )
    (net (code "71") (name "unconnected-(U4A-TXD0{slash}PA6-Pad34)") (class "Default")
      (node (ref "U4") (pin "34") (pinfunction "TXD0/PA6_34") (pintype "bidirectional"))
    )
    (net (code "72") (name "unconnected-(U5-BYP-Pad4)") (class "Default")
      (node (ref "U5") (pin "4") (pinfunction "BYP_4") (pintype "passive+no_connect"))
    )
    (net (code "73") (name "unconnected-(U6-NC-Pad6)") (class "Default")
      (node (ref "U6") (pin "6") (pinfunction "NC_6") (pintype "passive+no_connect"))
    )
    (net (code "74") (name "unconnected-(U6-PGOOD-Pad4)") (class "Default")
      (node (ref "U6") (pin "4") (pinfunction "PGOOD_4") (pintype "output+no_connect"))
    )
  )
)
